# Schit.net
KiCad netlist of a schematic drawn in EAGLE
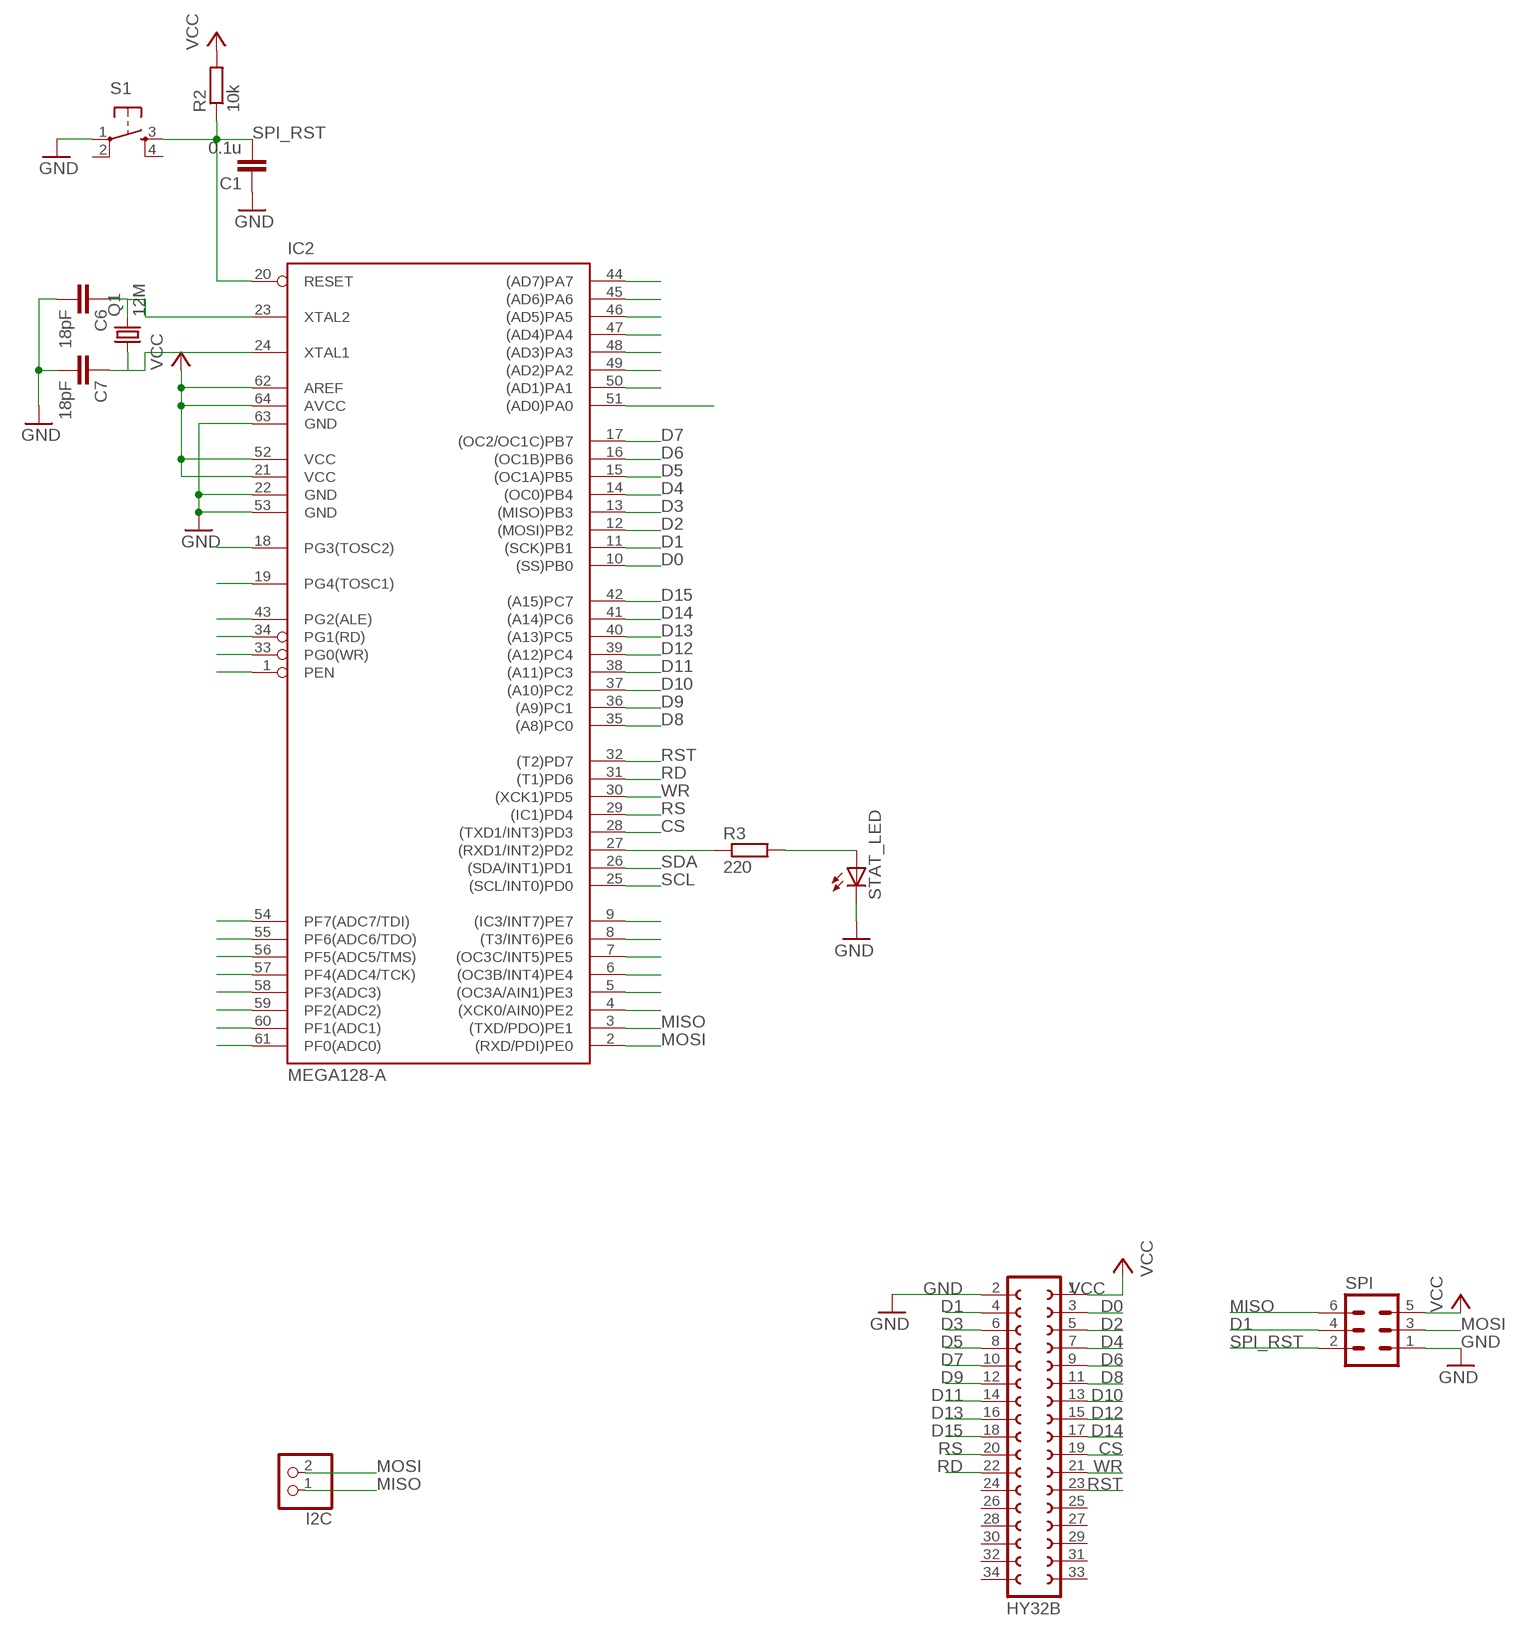
[diagram p0: schematic, sheet 1]

(export (version "E")
  (design (tool "Eeschema 10.0.6"))
  (components
    (comp (ref "C1")
      (value "0.1u")
      (footprint "eagle-import:C0805")
      (libsource (lib "eagle-import") (part "C-EUC0805"))
    )
    (comp (ref "C6")
      (value "18pF")
      (footprint "eagle-import:C0805")
      (libsource (lib "eagle-import") (part "C-EUC0805"))
    )
    (comp (ref "C7")
      (value "18pF")
      (footprint "eagle-import:C0805")
      (libsource (lib "eagle-import") (part "C-EUC0805"))
    )
    (comp (ref "HY32B")
      (value "FE17-2")
      (footprint "eagle-import:FE17-2")
      (libsource (lib "eagle-import") (part "FE17-2"))
    )
    (comp (ref "I2C")
      (value "PINHD-1X2")
      (footprint "eagle-import:1X02")
      (libsource (lib "eagle-import") (part "PINHD-1X2"))
    )
    (comp (ref "IC2")
      (value "MEGA128-A")
      (footprint "eagle-import:TQFP64")
      (fields (field (name "MPN") "ATMEGA128-16AU"))
      (libsource (lib "eagle-import") (part "MEGA128-A"))
    )
    (comp (ref "Q1")
      (value "12M")
      (footprint "eagle-import:HC49_S")
      (libsource (lib "eagle-import") (part "CRYSTALHC49S"))
    )
    (comp (ref "R2")
      (value "10k")
      (footprint "eagle-import:R0805")
      (libsource (lib "eagle-import") (part "R-EU_R0805"))
    )
    (comp (ref "R3")
      (value "220")
      (footprint "eagle-import:M2012")
      (libsource (lib "eagle-import") (part "R-EU_M2012"))
    )
    (comp (ref "S1")
      (value "TAC_SWITCHSMD")
      (footprint "eagle-import:TACTILE_SWITCH_SMD")
      (libsource (lib "eagle-import") (part "TAC_SWITCHSMD"))
    )
    (comp (ref "SPI")
      (value "ML6")
      (footprint "eagle-import:ML6")
      (libsource (lib "eagle-import") (part "ML6"))
    )
    (comp (ref "STAT_LED")
      (value "LED3MM")
      (footprint "eagle-import:LED3MM")
      (libsource (lib "eagle-import") (part "LED3MM"))
    )
  )
  (nets
    (net (code "1") (name "/CS") (class "Default")
      (node (ref "HY32B") (pin "19") (pinfunction "19_19") (pintype "passive"))
      (node (ref "IC2") (pin "28") (pinfunction "(TXD1/INT3)PD3_28") (pintype "bidirectional"))
    )
    (net (code "2") (name "/D0") (class "Default")
      (node (ref "HY32B") (pin "3") (pinfunction "3_3") (pintype "passive"))
      (node (ref "IC2") (pin "10") (pinfunction "(SS)PB0_10") (pintype "bidirectional"))
    )
    (net (code "3") (name "/D1") (class "Default")
      (node (ref "HY32B") (pin "4") (pinfunction "4_4") (pintype "passive"))
      (node (ref "IC2") (pin "11") (pinfunction "(SCK)PB1_11") (pintype "bidirectional"))
      (node (ref "SPI") (pin "4") (pinfunction "4_4") (pintype "passive"))
    )
    (net (code "4") (name "/D2") (class "Default")
      (node (ref "HY32B") (pin "5") (pinfunction "5_5") (pintype "passive"))
      (node (ref "IC2") (pin "12") (pinfunction "(MOSI)PB2_12") (pintype "bidirectional"))
    )
    (net (code "5") (name "/D3") (class "Default")
      (node (ref "HY32B") (pin "6") (pinfunction "6_6") (pintype "passive"))
      (node (ref "IC2") (pin "13") (pinfunction "(MISO)PB3_13") (pintype "bidirectional"))
    )
    (net (code "6") (name "/D4") (class "Default")
      (node (ref "HY32B") (pin "7") (pinfunction "7_7") (pintype "passive"))
      (node (ref "IC2") (pin "14") (pinfunction "(OC0)PB4_14") (pintype "bidirectional"))
    )
    (net (code "7") (name "/D5") (class "Default")
      (node (ref "HY32B") (pin "8") (pinfunction "8_8") (pintype "passive"))
      (node (ref "IC2") (pin "15") (pinfunction "(OC1A)PB5_15") (pintype "bidirectional"))
    )
    (net (code "8") (name "/D6") (class "Default")
      (node (ref "HY32B") (pin "9") (pinfunction "9_9") (pintype "passive"))
      (node (ref "IC2") (pin "16") (pinfunction "(OC1B)PB6_16") (pintype "bidirectional"))
    )
    (net (code "9") (name "/D7") (class "Default")
      (node (ref "HY32B") (pin "10") (pinfunction "10_10") (pintype "passive"))
      (node (ref "IC2") (pin "17") (pinfunction "(OC2/OC1C)PB7_17") (pintype "bidirectional"))
    )
    (net (code "10") (name "/D8") (class "Default")
      (node (ref "HY32B") (pin "11") (pinfunction "11_11") (pintype "passive"))
      (node (ref "IC2") (pin "35") (pinfunction "(A8)PC0_35") (pintype "output"))
    )
    (net (code "11") (name "/D9") (class "Default")
      (node (ref "HY32B") (pin "12") (pinfunction "12_12") (pintype "passive"))
      (node (ref "IC2") (pin "36") (pinfunction "(A9)PC1_36") (pintype "output"))
    )
    (net (code "12") (name "/D10") (class "Default")
      (node (ref "HY32B") (pin "13") (pinfunction "13_13") (pintype "passive"))
      (node (ref "IC2") (pin "37") (pinfunction "(A10)PC2_37") (pintype "output"))
    )
    (net (code "13") (name "/D11") (class "Default")
      (node (ref "HY32B") (pin "14") (pinfunction "14_14") (pintype "passive"))
      (node (ref "IC2") (pin "38") (pinfunction "(A11)PC3_38") (pintype "output"))
    )
    (net (code "14") (name "/D12") (class "Default")
      (node (ref "HY32B") (pin "15") (pinfunction "15_15") (pintype "passive"))
      (node (ref "IC2") (pin "39") (pinfunction "(A12)PC4_39") (pintype "output"))
    )
    (net (code "15") (name "/D13") (class "Default")
      (node (ref "HY32B") (pin "16") (pinfunction "16_16") (pintype "passive"))
      (node (ref "IC2") (pin "40") (pinfunction "(A13)PC5_40") (pintype "output"))
    )
    (net (code "16") (name "/D14") (class "Default")
      (node (ref "HY32B") (pin "17") (pinfunction "17_17") (pintype "passive"))
      (node (ref "IC2") (pin "41") (pinfunction "(A14)PC6_41") (pintype "output"))
    )
    (net (code "17") (name "/D15") (class "Default")
      (node (ref "HY32B") (pin "18") (pinfunction "18_18") (pintype "passive"))
      (node (ref "IC2") (pin "42") (pinfunction "(A15)PC7_42") (pintype "output"))
    )
    (net (code "18") (name "/MISO") (class "Default")
      (node (ref "I2C") (pin "1") (pinfunction "1_1") (pintype "passive"))
      (node (ref "IC2") (pin "3") (pinfunction "(TXD/PDO)PE1_3") (pintype "bidirectional"))
      (node (ref "SPI") (pin "6") (pinfunction "6_6") (pintype "passive"))
    )
    (net (code "19") (name "/MOSI") (class "Default")
      (node (ref "I2C") (pin "2") (pinfunction "2_2") (pintype "passive"))
      (node (ref "IC2") (pin "2") (pinfunction "(RXD/PDI)PE0_2") (pintype "bidirectional"))
      (node (ref "SPI") (pin "3") (pinfunction "3_3") (pintype "passive"))
    )
    (net (code "20") (name "/RD") (class "Default")
      (node (ref "HY32B") (pin "22") (pinfunction "22_22") (pintype "passive"))
      (node (ref "IC2") (pin "31") (pinfunction "(T1)PD6_31") (pintype "bidirectional"))
    )
    (net (code "21") (name "/RS") (class "Default")
      (node (ref "HY32B") (pin "20") (pinfunction "20_20") (pintype "passive"))
      (node (ref "IC2") (pin "29") (pinfunction "(IC1)PD4_29") (pintype "bidirectional"))
    )
    (net (code "22") (name "/RST") (class "Default")
      (node (ref "HY32B") (pin "23") (pinfunction "23_23") (pintype "passive"))
      (node (ref "IC2") (pin "32") (pinfunction "(T2)PD7_32") (pintype "bidirectional"))
    )
    (net (code "23") (name "/SCL") (class "Default")
      (node (ref "IC2") (pin "25") (pinfunction "(SCL/INT0)PD0_25") (pintype "bidirectional"))
    )
    (net (code "24") (name "/SDA") (class "Default")
      (node (ref "IC2") (pin "26") (pinfunction "(SDA/INT1)PD1_26") (pintype "bidirectional"))
    )
    (net (code "25") (name "/SPI_RST") (class "Default")
      (node (ref "C1") (pin "2") (pinfunction "2_2") (pintype "passive"))
      (node (ref "IC2") (pin "20") (pinfunction "RESET_20") (pintype "input"))
      (node (ref "R2") (pin "1") (pinfunction "1_1") (pintype "passive"))
      (node (ref "S1") (pin "3") (pinfunction "3_3") (pintype "passive"))
      (node (ref "SPI") (pin "2") (pinfunction "2_2") (pintype "passive"))
    )
    (net (code "26") (name "/WR") (class "Default")
      (node (ref "HY32B") (pin "21") (pinfunction "21_21") (pintype "passive"))
      (node (ref "IC2") (pin "30") (pinfunction "(XCK1)PD5_30") (pintype "bidirectional"))
    )
    (net (code "27") (name "GND") (class "Default")
      (node (ref "C1") (pin "1") (pinfunction "1_1") (pintype "passive"))
      (node (ref "C6") (pin "2") (pinfunction "2_2") (pintype "passive"))
      (node (ref "C7") (pin "2") (pinfunction "2_2") (pintype "passive"))
      (node (ref "HY32B") (pin "2") (pinfunction "2_2") (pintype "passive"))
      (node (ref "IC2") (pin "22") (pinfunction "GND_22") (pintype "power_in"))
      (node (ref "IC2") (pin "53") (pinfunction "GND_53") (pintype "power_in"))
      (node (ref "IC2") (pin "63") (pinfunction "GND_63") (pintype "power_in"))
      (node (ref "S1") (pin "1") (pinfunction "1_1") (pintype "passive"))
      (node (ref "SPI") (pin "1") (pinfunction "1_1") (pintype "passive"))
      (node (ref "STAT_LED") (pin "K") (pinfunction "C_K") (pintype "passive"))
    )
    (net (code "28") (name "Net-(IC2-(RXD1{slash}INT2)PD2)") (class "Default")
      (node (ref "IC2") (pin "27") (pinfunction "(RXD1/INT2)PD2_27") (pintype "bidirectional"))
      (node (ref "R3") (pin "1") (pinfunction "1_1") (pintype "passive"))
    )
    (net (code "29") (name "Net-(IC2-XTAL1)") (class "Default")
      (node (ref "C7") (pin "1") (pinfunction "1_1") (pintype "passive"))
      (node (ref "IC2") (pin "24") (pinfunction "XTAL1_24") (pintype "bidirectional"))
      (node (ref "Q1") (pin "1") (pinfunction "1_1") (pintype "passive"))
    )
    (net (code "30") (name "Net-(IC2-XTAL2)") (class "Default")
      (node (ref "C6") (pin "1") (pinfunction "1_1") (pintype "passive"))
      (node (ref "IC2") (pin "23") (pinfunction "XTAL2_23") (pintype "bidirectional"))
      (node (ref "Q1") (pin "2") (pinfunction "2_2") (pintype "passive"))
    )
    (net (code "31") (name "Net-(R3-Pad2)") (class "Default")
      (node (ref "R3") (pin "2") (pinfunction "2_2") (pintype "passive"))
      (node (ref "STAT_LED") (pin "A") (pinfunction "A_A") (pintype "passive"))
    )
    (net (code "32") (name "VCC") (class "Default")
      (node (ref "HY32B") (pin "1") (pinfunction "1_1") (pintype "passive"))
      (node (ref "IC2") (pin "21") (pinfunction "VCC_21") (pintype "power_in"))
      (node (ref "IC2") (pin "52") (pinfunction "VCC_52") (pintype "power_in"))
      (node (ref "IC2") (pin "62") (pinfunction "AREF_62") (pintype "passive"))
      (node (ref "IC2") (pin "64") (pinfunction "AVCC_64") (pintype "power_in"))
      (node (ref "R2") (pin "2") (pinfunction "2_2") (pintype "passive"))
      (node (ref "SPI") (pin "5") (pinfunction "5_5") (pintype "passive"))
    )
    (net (code "33") (name "unconnected-(HY32B-Pad24)") (class "Default")
      (node (ref "HY32B") (pin "24") (pinfunction "24_24") (pintype "passive"))
    )
    (net (code "34") (name "unconnected-(HY32B-Pad25)") (class "Default")
      (node (ref "HY32B") (pin "25") (pinfunction "25_25") (pintype "passive"))
    )
    (net (code "35") (name "unconnected-(HY32B-Pad26)") (class "Default")
      (node (ref "HY32B") (pin "26") (pinfunction "26_26") (pintype "passive"))
    )
    (net (code "36") (name "unconnected-(HY32B-Pad27)") (class "Default")
      (node (ref "HY32B") (pin "27") (pinfunction "27_27") (pintype "passive"))
    )
    (net (code "37") (name "unconnected-(HY32B-Pad28)") (class "Default")
      (node (ref "HY32B") (pin "28") (pinfunction "28_28") (pintype "passive"))
    )
    (net (code "38") (name "unconnected-(HY32B-Pad29)") (class "Default")
      (node (ref "HY32B") (pin "29") (pinfunction "29_29") (pintype "passive"))
    )
    (net (code "39") (name "unconnected-(HY32B-Pad30)") (class "Default")
      (node (ref "HY32B") (pin "30") (pinfunction "30_30") (pintype "passive"))
    )
    (net (code "40") (name "unconnected-(HY32B-Pad31)") (class "Default")
      (node (ref "HY32B") (pin "31") (pinfunction "31_31") (pintype "passive"))
    )
    (net (code "41") (name "unconnected-(HY32B-Pad32)") (class "Default")
      (node (ref "HY32B") (pin "32") (pinfunction "32_32") (pintype "passive"))
    )
    (net (code "42") (name "unconnected-(HY32B-Pad33)") (class "Default")
      (node (ref "HY32B") (pin "33") (pinfunction "33_33") (pintype "passive"))
    )
    (net (code "43") (name "unconnected-(HY32B-Pad34)") (class "Default")
      (node (ref "HY32B") (pin "34") (pinfunction "34_34") (pintype "passive"))
    )
    (net (code "44") (name "unconnected-(IC2-(AD0)PA0-Pad51)") (class "Default")
      (node (ref "IC2") (pin "51") (pinfunction "(AD0)PA0_51") (pintype "bidirectional"))
    )
    (net (code "45") (name "unconnected-(IC2-(AD1)PA1-Pad50)") (class "Default")
      (node (ref "IC2") (pin "50") (pinfunction "(AD1)PA1_50") (pintype "bidirectional"))
    )
    (net (code "46") (name "unconnected-(IC2-(AD2)PA2-Pad49)") (class "Default")
      (node (ref "IC2") (pin "49") (pinfunction "(AD2)PA2_49") (pintype "bidirectional"))
    )
    (net (code "47") (name "unconnected-(IC2-(AD3)PA3-Pad48)") (class "Default")
      (node (ref "IC2") (pin "48") (pinfunction "(AD3)PA3_48") (pintype "bidirectional"))
    )
    (net (code "48") (name "unconnected-(IC2-(AD4)PA4-Pad47)") (class "Default")
      (node (ref "IC2") (pin "47") (pinfunction "(AD4)PA4_47") (pintype "bidirectional"))
    )
    (net (code "49") (name "unconnected-(IC2-(AD5)PA5-Pad46)") (class "Default")
      (node (ref "IC2") (pin "46") (pinfunction "(AD5)PA5_46") (pintype "bidirectional"))
    )
    (net (code "50") (name "unconnected-(IC2-(AD6)PA6-Pad45)") (class "Default")
      (node (ref "IC2") (pin "45") (pinfunction "(AD6)PA6_45") (pintype "bidirectional"))
    )
    (net (code "51") (name "unconnected-(IC2-(AD7)PA7-Pad44)") (class "Default")
      (node (ref "IC2") (pin "44") (pinfunction "(AD7)PA7_44") (pintype "bidirectional"))
    )
    (net (code "52") (name "unconnected-(IC2-(IC3{slash}INT7)PE7-Pad9)") (class "Default")
      (node (ref "IC2") (pin "9") (pinfunction "(IC3/INT7)PE7_9") (pintype "bidirectional"))
    )
    (net (code "53") (name "unconnected-(IC2-(OC3A{slash}AIN1)PE3-Pad5)") (class "Default")
      (node (ref "IC2") (pin "5") (pinfunction "(OC3A/AIN1)PE3_5") (pintype "bidirectional"))
    )
    (net (code "54") (name "unconnected-(IC2-(OC3B{slash}INT4)PE4-Pad6)") (class "Default")
      (node (ref "IC2") (pin "6") (pinfunction "(OC3B/INT4)PE4_6") (pintype "bidirectional"))
    )
    (net (code "55") (name "unconnected-(IC2-(OC3C{slash}INT5)PE5-Pad7)") (class "Default")
      (node (ref "IC2") (pin "7") (pinfunction "(OC3C/INT5)PE5_7") (pintype "bidirectional"))
    )
    (net (code "56") (name "unconnected-(IC2-(T3{slash}INT6)PE6-Pad8)") (class "Default")
      (node (ref "IC2") (pin "8") (pinfunction "(T3/INT6)PE6_8") (pintype "bidirectional"))
    )
    (net (code "57") (name "unconnected-(IC2-(XCK0{slash}AIN0)PE2-Pad4)") (class "Default")
      (node (ref "IC2") (pin "4") (pinfunction "(XCK0/AIN0)PE2_4") (pintype "bidirectional"))
    )
    (net (code "58") (name "unconnected-(IC2-PEN-Pad1)") (class "Default")
      (node (ref "IC2") (pin "1") (pinfunction "PEN_1") (pintype "input"))
    )
    (net (code "59") (name "unconnected-(IC2-PF0(ADC0)-Pad61)") (class "Default")
      (node (ref "IC2") (pin "61") (pinfunction "PF0(ADC0)_61") (pintype "input"))
    )
    (net (code "60") (name "unconnected-(IC2-PF1(ADC1)-Pad60)") (class "Default")
      (node (ref "IC2") (pin "60") (pinfunction "PF1(ADC1)_60") (pintype "input"))
    )
    (net (code "61") (name "unconnected-(IC2-PF2(ADC2)-Pad59)") (class "Default")
      (node (ref "IC2") (pin "59") (pinfunction "PF2(ADC2)_59") (pintype "input"))
    )
    (net (code "62") (name "unconnected-(IC2-PF3(ADC3)-Pad58)") (class "Default")
      (node (ref "IC2") (pin "58") (pinfunction "PF3(ADC3)_58") (pintype "input"))
    )
    (net (code "63") (name "unconnected-(IC2-PF4(ADC4{slash}TCK)-Pad57)") (class "Default")
      (node (ref "IC2") (pin "57") (pinfunction "PF4(ADC4/TCK)_57") (pintype "input"))
    )
    (net (code "64") (name "unconnected-(IC2-PF5(ADC5{slash}TMS)-Pad56)") (class "Default")
      (node (ref "IC2") (pin "56") (pinfunction "PF5(ADC5/TMS)_56") (pintype "input"))
    )
    (net (code "65") (name "unconnected-(IC2-PF6(ADC6{slash}TDO)-Pad55)") (class "Default")
      (node (ref "IC2") (pin "55") (pinfunction "PF6(ADC6/TDO)_55") (pintype "input"))
    )
    (net (code "66") (name "unconnected-(IC2-PF7(ADC7{slash}TDI)-Pad54)") (class "Default")
      (node (ref "IC2") (pin "54") (pinfunction "PF7(ADC7/TDI)_54") (pintype "input"))
    )
    (net (code "67") (name "unconnected-(IC2-PG0(WR)-Pad33)") (class "Default")
      (node (ref "IC2") (pin "33") (pinfunction "PG0(WR)_33") (pintype "bidirectional"))
    )
    (net (code "68") (name "unconnected-(IC2-PG1(RD)-Pad34)") (class "Default")
      (node (ref "IC2") (pin "34") (pinfunction "PG1(RD)_34") (pintype "bidirectional"))
    )
    (net (code "69") (name "unconnected-(IC2-PG2(ALE)-Pad43)") (class "Default")
      (node (ref "IC2") (pin "43") (pinfunction "PG2(ALE)_43") (pintype "bidirectional"))
    )
    (net (code "70") (name "unconnected-(IC2-PG3(TOSC2)-Pad18)") (class "Default")
      (node (ref "IC2") (pin "18") (pinfunction "PG3(TOSC2)_18") (pintype "bidirectional"))
    )
    (net (code "71") (name "unconnected-(IC2-PG4(TOSC1)-Pad19)") (class "Default")
      (node (ref "IC2") (pin "19") (pinfunction "PG4(TOSC1)_19") (pintype "bidirectional"))
    )
    (net (code "72") (name "unconnected-(S1-Pad2)") (class "Default")
      (node (ref "S1") (pin "2") (pinfunction "2_2") (pintype "passive"))
    )
    (net (code "73") (name "unconnected-(S1-Pad4)") (class "Default")
      (node (ref "S1") (pin "4") (pinfunction "4_4") (pintype "passive"))
    )
  )
)
